# ledboard-r2.net
KiCad netlist of a schematic drawn in EAGLE
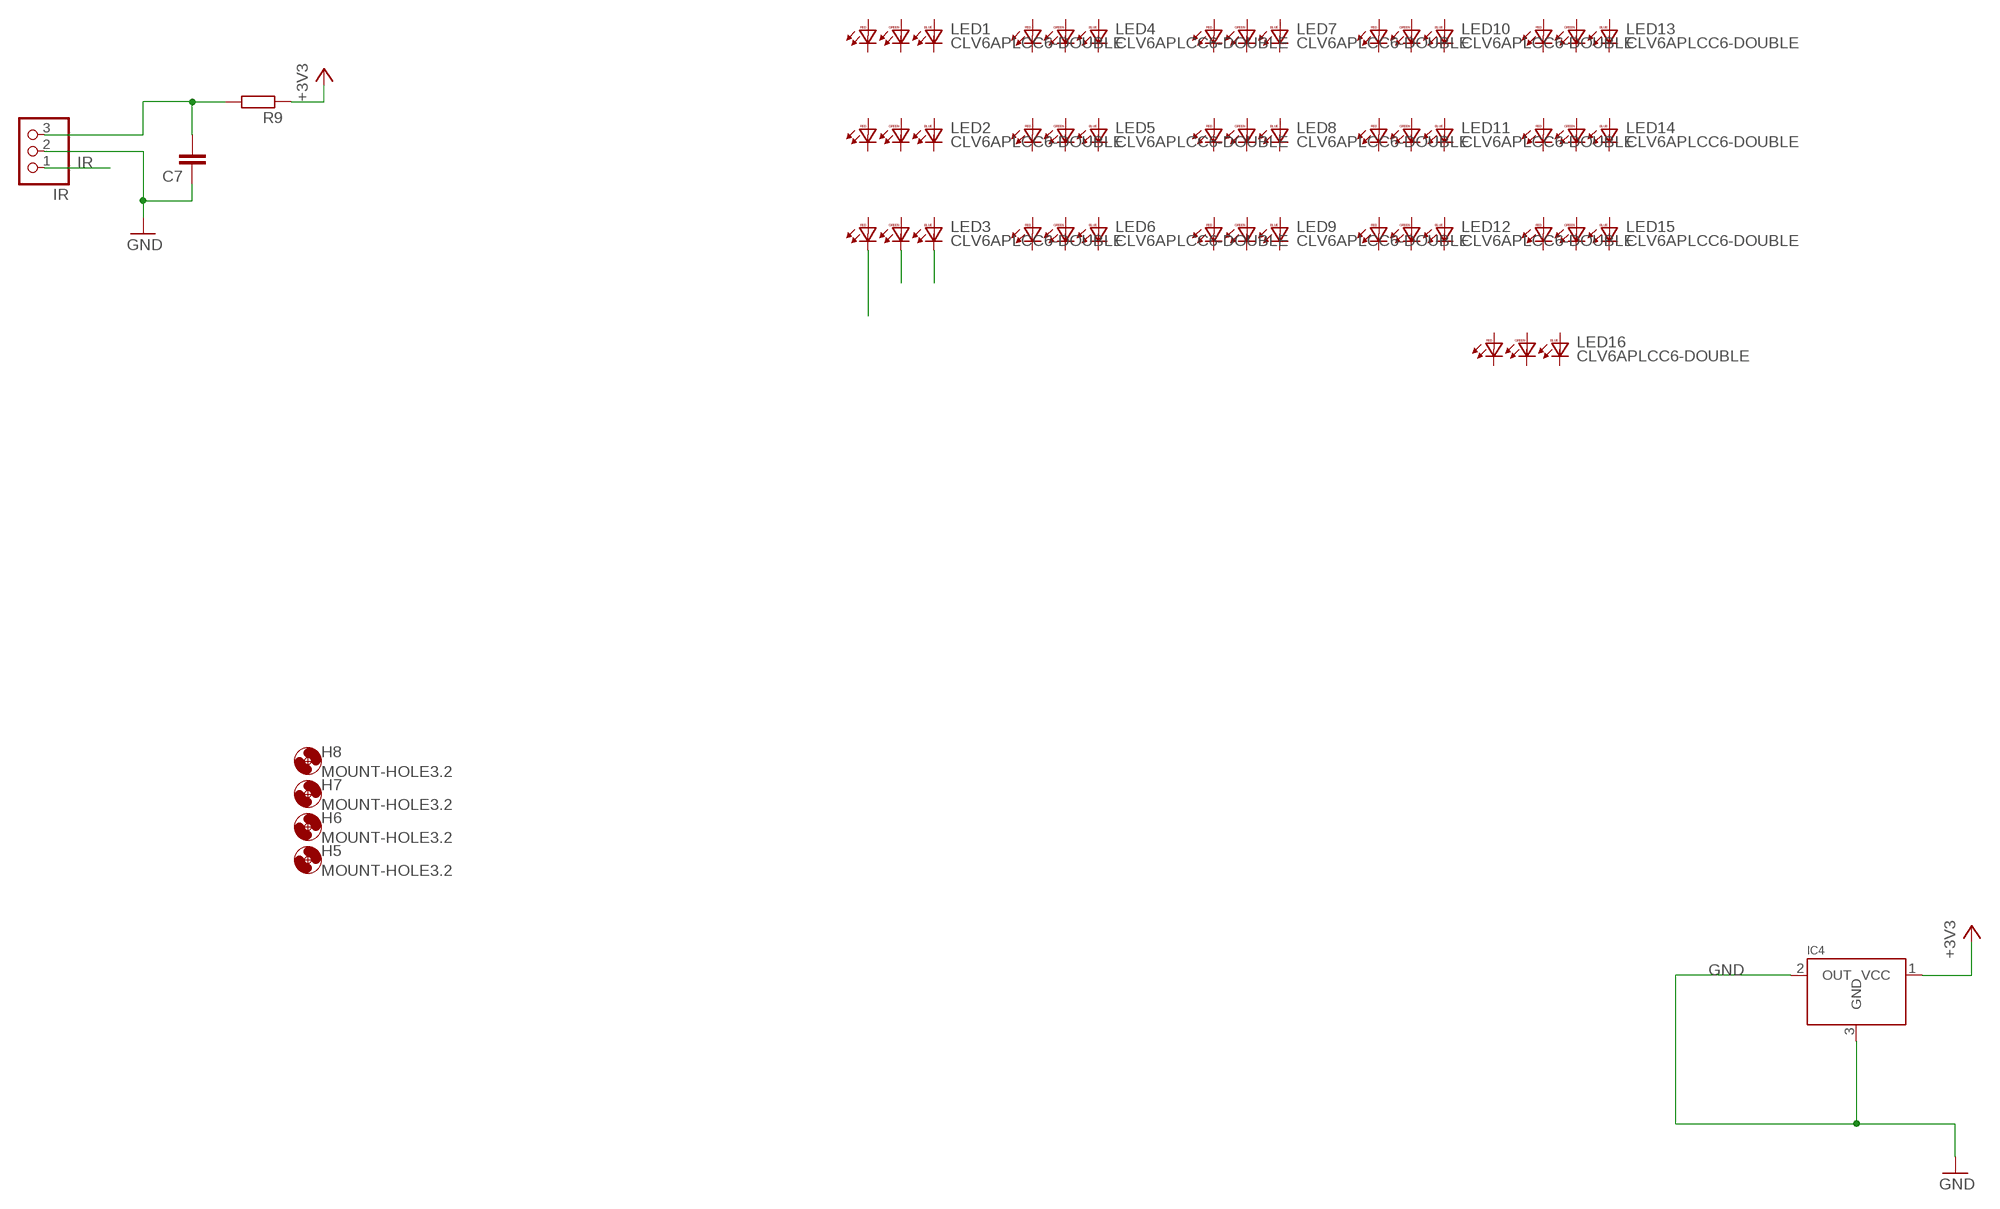
[diagram p0: schematic, sheet 1]

(export (version "E")
  (design (tool "Eeschema 10.0.6"))
  (components
    (comp (ref "C7")
      (value "C-EUC0805")
      (footprint "eagle-import:C0805")
      (libsource (lib "eagle-import") (part "C-EUC0805"))
    )
    (comp (ref "H5")
      (value "MOUNT-HOLE3.2")
      (footprint "eagle-import:3,2")
      (libsource (lib "eagle-import") (part "MOUNT-HOLE3.2"))
    )
    (comp (ref "H6")
      (value "MOUNT-HOLE3.2")
      (footprint "eagle-import:3,2")
      (libsource (lib "eagle-import") (part "MOUNT-HOLE3.2"))
    )
    (comp (ref "H7")
      (value "MOUNT-HOLE3.2")
      (footprint "eagle-import:3,2")
      (libsource (lib "eagle-import") (part "MOUNT-HOLE3.2"))
    )
    (comp (ref "H8")
      (value "MOUNT-HOLE3.2")
      (footprint "eagle-import:3,2")
      (libsource (lib "eagle-import") (part "MOUNT-HOLE3.2"))
    )
    (comp (ref "IC4")
      (value "MCP9701T-E/TTCTREFLOW")
      (footprint "eagle-import:SOT23-R")
      (libsource (lib "eagle-import") (part "MCP9701T-E/TTCTREFLOW"))
    )
    (comp (ref "IR")
      (value "PINHD-1X3")
      (footprint "eagle-import:1X03")
      (libsource (lib "eagle-import") (part "PINHD-1X3"))
    )
    (comp (ref "LED1")
      (value "CLV6APLCC6-DOUBLE")
      (footprint "eagle-import:PLCC6-DOUBLE")
      (libsource (lib "eagle-import") (part "CLV6APLCC6-DOUBLE"))
    )
    (comp (ref "LED2")
      (value "CLV6APLCC6-DOUBLE")
      (footprint "eagle-import:PLCC6-DOUBLE")
      (libsource (lib "eagle-import") (part "CLV6APLCC6-DOUBLE"))
    )
    (comp (ref "LED3")
      (value "CLV6APLCC6-DOUBLE")
      (footprint "eagle-import:PLCC6-DOUBLE")
      (libsource (lib "eagle-import") (part "CLV6APLCC6-DOUBLE"))
    )
    (comp (ref "LED4")
      (value "CLV6APLCC6-DOUBLE")
      (footprint "eagle-import:PLCC6-DOUBLE")
      (libsource (lib "eagle-import") (part "CLV6APLCC6-DOUBLE"))
    )
    (comp (ref "LED5")
      (value "CLV6APLCC6-DOUBLE")
      (footprint "eagle-import:PLCC6-DOUBLE")
      (libsource (lib "eagle-import") (part "CLV6APLCC6-DOUBLE"))
    )
    (comp (ref "LED6")
      (value "CLV6APLCC6-DOUBLE")
      (footprint "eagle-import:PLCC6-DOUBLE")
      (libsource (lib "eagle-import") (part "CLV6APLCC6-DOUBLE"))
    )
    (comp (ref "LED7")
      (value "CLV6APLCC6-DOUBLE")
      (footprint "eagle-import:PLCC6-DOUBLE")
      (libsource (lib "eagle-import") (part "CLV6APLCC6-DOUBLE"))
    )
    (comp (ref "LED8")
      (value "CLV6APLCC6-DOUBLE")
      (footprint "eagle-import:PLCC6-DOUBLE")
      (libsource (lib "eagle-import") (part "CLV6APLCC6-DOUBLE"))
    )
    (comp (ref "LED9")
      (value "CLV6APLCC6-DOUBLE")
      (footprint "eagle-import:PLCC6-DOUBLE")
      (libsource (lib "eagle-import") (part "CLV6APLCC6-DOUBLE"))
    )
    (comp (ref "LED10")
      (value "CLV6APLCC6-DOUBLE")
      (footprint "eagle-import:PLCC6-DOUBLE")
      (libsource (lib "eagle-import") (part "CLV6APLCC6-DOUBLE"))
    )
    (comp (ref "LED11")
      (value "CLV6APLCC6-DOUBLE")
      (footprint "eagle-import:PLCC6-DOUBLE")
      (libsource (lib "eagle-import") (part "CLV6APLCC6-DOUBLE"))
    )
    (comp (ref "LED12")
      (value "CLV6APLCC6-DOUBLE")
      (footprint "eagle-import:PLCC6-DOUBLE")
      (libsource (lib "eagle-import") (part "CLV6APLCC6-DOUBLE"))
    )
    (comp (ref "LED13")
      (value "CLV6APLCC6-DOUBLE")
      (footprint "eagle-import:PLCC6-DOUBLE")
      (libsource (lib "eagle-import") (part "CLV6APLCC6-DOUBLE"))
    )
    (comp (ref "LED14")
      (value "CLV6APLCC6-DOUBLE")
      (footprint "eagle-import:PLCC6-DOUBLE")
      (libsource (lib "eagle-import") (part "CLV6APLCC6-DOUBLE"))
    )
    (comp (ref "LED15")
      (value "CLV6APLCC6-DOUBLE")
      (footprint "eagle-import:PLCC6-DOUBLE")
      (libsource (lib "eagle-import") (part "CLV6APLCC6-DOUBLE"))
    )
    (comp (ref "LED16")
      (value "CLV6APLCC6-DOUBLE")
      (footprint "eagle-import:PLCC6-DOUBLE")
      (libsource (lib "eagle-import") (part "CLV6APLCC6-DOUBLE"))
    )
    (comp (ref "R9")
      (value "R-EU_R0805")
      (footprint "eagle-import:R0805")
      (libsource (lib "eagle-import") (part "R-EU_R0805"))
    )
  )
  (nets
    (net (code "1") (name "+3V3") (class "Default")
      (node (ref "IC4") (pin "1") (pinfunction "VCC_1") (pintype "power_in"))
      (node (ref "R9") (pin "1") (pinfunction "1_1") (pintype "passive"))
    )
    (net (code "2") (name "/IR") (class "Default")
      (node (ref "IR") (pin "1") (pinfunction "1_1") (pintype "passive"))
    )
    (net (code "3") (name "GND") (class "Default")
      (node (ref "C7") (pin "1") (pinfunction "1_1") (pintype "passive"))
      (node (ref "IC4") (pin "2") (pinfunction "OUT_2") (pintype "bidirectional"))
      (node (ref "IC4") (pin "3") (pinfunction "GND_3") (pintype "power_in"))
      (node (ref "IR") (pin "2") (pinfunction "2_2") (pintype "passive"))
    )
    (net (code "4") (name "Net-(C7-Pad2)") (class "Default")
      (node (ref "C7") (pin "2") (pinfunction "2_2") (pintype "passive"))
      (node (ref "IR") (pin "3") (pinfunction "3_3") (pintype "passive"))
      (node (ref "R9") (pin "2") (pinfunction "2_2") (pintype "passive"))
    )
    (net (code "5") (name "unconnected-(LED1-BA-Pad6)") (class "Default")
      (node (ref "LED1") (pin "6") (pinfunction "BA_6") (pintype "passive"))
    )
    (net (code "6") (name "unconnected-(LED1-BC-Pad1)") (class "Default")
      (node (ref "LED1") (pin "1") (pinfunction "BC_1") (pintype "passive"))
    )
    (net (code "7") (name "unconnected-(LED1-GA-Pad5)") (class "Default")
      (node (ref "LED1") (pin "5") (pinfunction "GA_5") (pintype "passive"))
    )
    (net (code "8") (name "unconnected-(LED1-GC-Pad2)") (class "Default")
      (node (ref "LED1") (pin "2") (pinfunction "GC_2") (pintype "passive"))
    )
    (net (code "9") (name "unconnected-(LED1-RA-Pad4)") (class "Default")
      (node (ref "LED1") (pin "4") (pinfunction "RA_4") (pintype "passive"))
    )
    (net (code "10") (name "unconnected-(LED1-RC-Pad3)") (class "Default")
      (node (ref "LED1") (pin "3") (pinfunction "RC_3") (pintype "passive"))
    )
    (net (code "11") (name "unconnected-(LED2-BA-Pad6)") (class "Default")
      (node (ref "LED2") (pin "6") (pinfunction "BA_6") (pintype "passive"))
    )
    (net (code "12") (name "unconnected-(LED2-BC-Pad1)") (class "Default")
      (node (ref "LED2") (pin "1") (pinfunction "BC_1") (pintype "passive"))
    )
    (net (code "13") (name "unconnected-(LED2-GA-Pad5)") (class "Default")
      (node (ref "LED2") (pin "5") (pinfunction "GA_5") (pintype "passive"))
    )
    (net (code "14") (name "unconnected-(LED2-GC-Pad2)") (class "Default")
      (node (ref "LED2") (pin "2") (pinfunction "GC_2") (pintype "passive"))
    )
    (net (code "15") (name "unconnected-(LED2-RA-Pad4)") (class "Default")
      (node (ref "LED2") (pin "4") (pinfunction "RA_4") (pintype "passive"))
    )
    (net (code "16") (name "unconnected-(LED2-RC-Pad3)") (class "Default")
      (node (ref "LED2") (pin "3") (pinfunction "RC_3") (pintype "passive"))
    )
    (net (code "17") (name "unconnected-(LED3-BA-Pad6)") (class "Default")
      (node (ref "LED3") (pin "6") (pinfunction "BA_6") (pintype "passive"))
    )
    (net (code "18") (name "unconnected-(LED3-BC-Pad1)") (class "Default")
      (node (ref "LED3") (pin "1") (pinfunction "BC_1") (pintype "passive"))
    )
    (net (code "19") (name "unconnected-(LED3-GA-Pad5)") (class "Default")
      (node (ref "LED3") (pin "5") (pinfunction "GA_5") (pintype "passive"))
    )
    (net (code "20") (name "unconnected-(LED3-GC-Pad2)") (class "Default")
      (node (ref "LED3") (pin "2") (pinfunction "GC_2") (pintype "passive"))
    )
    (net (code "21") (name "unconnected-(LED3-RA-Pad4)") (class "Default")
      (node (ref "LED3") (pin "4") (pinfunction "RA_4") (pintype "passive"))
    )
    (net (code "22") (name "unconnected-(LED3-RC-Pad3)") (class "Default")
      (node (ref "LED3") (pin "3") (pinfunction "RC_3") (pintype "passive"))
    )
    (net (code "23") (name "unconnected-(LED4-BA-Pad6)") (class "Default")
      (node (ref "LED4") (pin "6") (pinfunction "BA_6") (pintype "passive"))
    )
    (net (code "24") (name "unconnected-(LED4-BC-Pad1)") (class "Default")
      (node (ref "LED4") (pin "1") (pinfunction "BC_1") (pintype "passive"))
    )
    (net (code "25") (name "unconnected-(LED4-GA-Pad5)") (class "Default")
      (node (ref "LED4") (pin "5") (pinfunction "GA_5") (pintype "passive"))
    )
    (net (code "26") (name "unconnected-(LED4-GC-Pad2)") (class "Default")
      (node (ref "LED4") (pin "2") (pinfunction "GC_2") (pintype "passive"))
    )
    (net (code "27") (name "unconnected-(LED4-RA-Pad4)") (class "Default")
      (node (ref "LED4") (pin "4") (pinfunction "RA_4") (pintype "passive"))
    )
    (net (code "28") (name "unconnected-(LED4-RC-Pad3)") (class "Default")
      (node (ref "LED4") (pin "3") (pinfunction "RC_3") (pintype "passive"))
    )
    (net (code "29") (name "unconnected-(LED5-BA-Pad6)") (class "Default")
      (node (ref "LED5") (pin "6") (pinfunction "BA_6") (pintype "passive"))
    )
    (net (code "30") (name "unconnected-(LED5-BC-Pad1)") (class "Default")
      (node (ref "LED5") (pin "1") (pinfunction "BC_1") (pintype "passive"))
    )
    (net (code "31") (name "unconnected-(LED5-GA-Pad5)") (class "Default")
      (node (ref "LED5") (pin "5") (pinfunction "GA_5") (pintype "passive"))
    )
    (net (code "32") (name "unconnected-(LED5-GC-Pad2)") (class "Default")
      (node (ref "LED5") (pin "2") (pinfunction "GC_2") (pintype "passive"))
    )
    (net (code "33") (name "unconnected-(LED5-RA-Pad4)") (class "Default")
      (node (ref "LED5") (pin "4") (pinfunction "RA_4") (pintype "passive"))
    )
    (net (code "34") (name "unconnected-(LED5-RC-Pad3)") (class "Default")
      (node (ref "LED5") (pin "3") (pinfunction "RC_3") (pintype "passive"))
    )
    (net (code "35") (name "unconnected-(LED6-BA-Pad6)") (class "Default")
      (node (ref "LED6") (pin "6") (pinfunction "BA_6") (pintype "passive"))
    )
    (net (code "36") (name "unconnected-(LED6-BC-Pad1)") (class "Default")
      (node (ref "LED6") (pin "1") (pinfunction "BC_1") (pintype "passive"))
    )
    (net (code "37") (name "unconnected-(LED6-GA-Pad5)") (class "Default")
      (node (ref "LED6") (pin "5") (pinfunction "GA_5") (pintype "passive"))
    )
    (net (code "38") (name "unconnected-(LED6-GC-Pad2)") (class "Default")
      (node (ref "LED6") (pin "2") (pinfunction "GC_2") (pintype "passive"))
    )
    (net (code "39") (name "unconnected-(LED6-RA-Pad4)") (class "Default")
      (node (ref "LED6") (pin "4") (pinfunction "RA_4") (pintype "passive"))
    )
    (net (code "40") (name "unconnected-(LED6-RC-Pad3)") (class "Default")
      (node (ref "LED6") (pin "3") (pinfunction "RC_3") (pintype "passive"))
    )
    (net (code "41") (name "unconnected-(LED7-BA-Pad6)") (class "Default")
      (node (ref "LED7") (pin "6") (pinfunction "BA_6") (pintype "passive"))
    )
    (net (code "42") (name "unconnected-(LED7-BC-Pad1)") (class "Default")
      (node (ref "LED7") (pin "1") (pinfunction "BC_1") (pintype "passive"))
    )
    (net (code "43") (name "unconnected-(LED7-GA-Pad5)") (class "Default")
      (node (ref "LED7") (pin "5") (pinfunction "GA_5") (pintype "passive"))
    )
    (net (code "44") (name "unconnected-(LED7-GC-Pad2)") (class "Default")
      (node (ref "LED7") (pin "2") (pinfunction "GC_2") (pintype "passive"))
    )
    (net (code "45") (name "unconnected-(LED7-RA-Pad4)") (class "Default")
      (node (ref "LED7") (pin "4") (pinfunction "RA_4") (pintype "passive"))
    )
    (net (code "46") (name "unconnected-(LED7-RC-Pad3)") (class "Default")
      (node (ref "LED7") (pin "3") (pinfunction "RC_3") (pintype "passive"))
    )
    (net (code "47") (name "unconnected-(LED8-BA-Pad6)") (class "Default")
      (node (ref "LED8") (pin "6") (pinfunction "BA_6") (pintype "passive"))
    )
    (net (code "48") (name "unconnected-(LED8-BC-Pad1)") (class "Default")
      (node (ref "LED8") (pin "1") (pinfunction "BC_1") (pintype "passive"))
    )
    (net (code "49") (name "unconnected-(LED8-GA-Pad5)") (class "Default")
      (node (ref "LED8") (pin "5") (pinfunction "GA_5") (pintype "passive"))
    )
    (net (code "50") (name "unconnected-(LED8-GC-Pad2)") (class "Default")
      (node (ref "LED8") (pin "2") (pinfunction "GC_2") (pintype "passive"))
    )
    (net (code "51") (name "unconnected-(LED8-RA-Pad4)") (class "Default")
      (node (ref "LED8") (pin "4") (pinfunction "RA_4") (pintype "passive"))
    )
    (net (code "52") (name "unconnected-(LED8-RC-Pad3)") (class "Default")
      (node (ref "LED8") (pin "3") (pinfunction "RC_3") (pintype "passive"))
    )
    (net (code "53") (name "unconnected-(LED9-BA-Pad6)") (class "Default")
      (node (ref "LED9") (pin "6") (pinfunction "BA_6") (pintype "passive"))
    )
    (net (code "54") (name "unconnected-(LED9-BC-Pad1)") (class "Default")
      (node (ref "LED9") (pin "1") (pinfunction "BC_1") (pintype "passive"))
    )
    (net (code "55") (name "unconnected-(LED9-GA-Pad5)") (class "Default")
      (node (ref "LED9") (pin "5") (pinfunction "GA_5") (pintype "passive"))
    )
    (net (code "56") (name "unconnected-(LED9-GC-Pad2)") (class "Default")
      (node (ref "LED9") (pin "2") (pinfunction "GC_2") (pintype "passive"))
    )
    (net (code "57") (name "unconnected-(LED9-RA-Pad4)") (class "Default")
      (node (ref "LED9") (pin "4") (pinfunction "RA_4") (pintype "passive"))
    )
    (net (code "58") (name "unconnected-(LED9-RC-Pad3)") (class "Default")
      (node (ref "LED9") (pin "3") (pinfunction "RC_3") (pintype "passive"))
    )
    (net (code "59") (name "unconnected-(LED10-BA-Pad6)") (class "Default")
      (node (ref "LED10") (pin "6") (pinfunction "BA_6") (pintype "passive"))
    )
    (net (code "60") (name "unconnected-(LED10-BC-Pad1)") (class "Default")
      (node (ref "LED10") (pin "1") (pinfunction "BC_1") (pintype "passive"))
    )
    (net (code "61") (name "unconnected-(LED10-GA-Pad5)") (class "Default")
      (node (ref "LED10") (pin "5") (pinfunction "GA_5") (pintype "passive"))
    )
    (net (code "62") (name "unconnected-(LED10-GC-Pad2)") (class "Default")
      (node (ref "LED10") (pin "2") (pinfunction "GC_2") (pintype "passive"))
    )
    (net (code "63") (name "unconnected-(LED10-RA-Pad4)") (class "Default")
      (node (ref "LED10") (pin "4") (pinfunction "RA_4") (pintype "passive"))
    )
    (net (code "64") (name "unconnected-(LED10-RC-Pad3)") (class "Default")
      (node (ref "LED10") (pin "3") (pinfunction "RC_3") (pintype "passive"))
    )
    (net (code "65") (name "unconnected-(LED11-BA-Pad6)") (class "Default")
      (node (ref "LED11") (pin "6") (pinfunction "BA_6") (pintype "passive"))
    )
    (net (code "66") (name "unconnected-(LED11-BC-Pad1)") (class "Default")
      (node (ref "LED11") (pin "1") (pinfunction "BC_1") (pintype "passive"))
    )
    (net (code "67") (name "unconnected-(LED11-GA-Pad5)") (class "Default")
      (node (ref "LED11") (pin "5") (pinfunction "GA_5") (pintype "passive"))
    )
    (net (code "68") (name "unconnected-(LED11-GC-Pad2)") (class "Default")
      (node (ref "LED11") (pin "2") (pinfunction "GC_2") (pintype "passive"))
    )
    (net (code "69") (name "unconnected-(LED11-RA-Pad4)") (class "Default")
      (node (ref "LED11") (pin "4") (pinfunction "RA_4") (pintype "passive"))
    )
    (net (code "70") (name "unconnected-(LED11-RC-Pad3)") (class "Default")
      (node (ref "LED11") (pin "3") (pinfunction "RC_3") (pintype "passive"))
    )
    (net (code "71") (name "unconnected-(LED12-BA-Pad6)") (class "Default")
      (node (ref "LED12") (pin "6") (pinfunction "BA_6") (pintype "passive"))
    )
    (net (code "72") (name "unconnected-(LED12-BC-Pad1)") (class "Default")
      (node (ref "LED12") (pin "1") (pinfunction "BC_1") (pintype "passive"))
    )
    (net (code "73") (name "unconnected-(LED12-GA-Pad5)") (class "Default")
      (node (ref "LED12") (pin "5") (pinfunction "GA_5") (pintype "passive"))
    )
    (net (code "74") (name "unconnected-(LED12-GC-Pad2)") (class "Default")
      (node (ref "LED12") (pin "2") (pinfunction "GC_2") (pintype "passive"))
    )
    (net (code "75") (name "unconnected-(LED12-RA-Pad4)") (class "Default")
      (node (ref "LED12") (pin "4") (pinfunction "RA_4") (pintype "passive"))
    )
    (net (code "76") (name "unconnected-(LED12-RC-Pad3)") (class "Default")
      (node (ref "LED12") (pin "3") (pinfunction "RC_3") (pintype "passive"))
    )
    (net (code "77") (name "unconnected-(LED13-BA-Pad6)") (class "Default")
      (node (ref "LED13") (pin "6") (pinfunction "BA_6") (pintype "passive"))
    )
    (net (code "78") (name "unconnected-(LED13-BC-Pad1)") (class "Default")
      (node (ref "LED13") (pin "1") (pinfunction "BC_1") (pintype "passive"))
    )
    (net (code "79") (name "unconnected-(LED13-GA-Pad5)") (class "Default")
      (node (ref "LED13") (pin "5") (pinfunction "GA_5") (pintype "passive"))
    )
    (net (code "80") (name "unconnected-(LED13-GC-Pad2)") (class "Default")
      (node (ref "LED13") (pin "2") (pinfunction "GC_2") (pintype "passive"))
    )
    (net (code "81") (name "unconnected-(LED13-RA-Pad4)") (class "Default")
      (node (ref "LED13") (pin "4") (pinfunction "RA_4") (pintype "passive"))
    )
    (net (code "82") (name "unconnected-(LED13-RC-Pad3)") (class "Default")
      (node (ref "LED13") (pin "3") (pinfunction "RC_3") (pintype "passive"))
    )
    (net (code "83") (name "unconnected-(LED14-BA-Pad6)") (class "Default")
      (node (ref "LED14") (pin "6") (pinfunction "BA_6") (pintype "passive"))
    )
    (net (code "84") (name "unconnected-(LED14-BC-Pad1)") (class "Default")
      (node (ref "LED14") (pin "1") (pinfunction "BC_1") (pintype "passive"))
    )
    (net (code "85") (name "unconnected-(LED14-GA-Pad5)") (class "Default")
      (node (ref "LED14") (pin "5") (pinfunction "GA_5") (pintype "passive"))
    )
    (net (code "86") (name "unconnected-(LED14-GC-Pad2)") (class "Default")
      (node (ref "LED14") (pin "2") (pinfunction "GC_2") (pintype "passive"))
    )
    (net (code "87") (name "unconnected-(LED14-RA-Pad4)") (class "Default")
      (node (ref "LED14") (pin "4") (pinfunction "RA_4") (pintype "passive"))
    )
    (net (code "88") (name "unconnected-(LED14-RC-Pad3)") (class "Default")
      (node (ref "LED14") (pin "3") (pinfunction "RC_3") (pintype "passive"))
    )
    (net (code "89") (name "unconnected-(LED15-BA-Pad6)") (class "Default")
      (node (ref "LED15") (pin "6") (pinfunction "BA_6") (pintype "passive"))
    )
    (net (code "90") (name "unconnected-(LED15-BC-Pad1)") (class "Default")
      (node (ref "LED15") (pin "1") (pinfunction "BC_1") (pintype "passive"))
    )
    (net (code "91") (name "unconnected-(LED15-GA-Pad5)") (class "Default")
      (node (ref "LED15") (pin "5") (pinfunction "GA_5") (pintype "passive"))
    )
    (net (code "92") (name "unconnected-(LED15-GC-Pad2)") (class "Default")
      (node (ref "LED15") (pin "2") (pinfunction "GC_2") (pintype "passive"))
    )
    (net (code "93") (name "unconnected-(LED15-RA-Pad4)") (class "Default")
      (node (ref "LED15") (pin "4") (pinfunction "RA_4") (pintype "passive"))
    )
    (net (code "94") (name "unconnected-(LED15-RC-Pad3)") (class "Default")
      (node (ref "LED15") (pin "3") (pinfunction "RC_3") (pintype "passive"))
    )
    (net (code "95") (name "unconnected-(LED16-BA-Pad6)") (class "Default")
      (node (ref "LED16") (pin "6") (pinfunction "BA_6") (pintype "passive"))
    )
    (net (code "96") (name "unconnected-(LED16-BC-Pad1)") (class "Default")
      (node (ref "LED16") (pin "1") (pinfunction "BC_1") (pintype "passive"))
    )
    (net (code "97") (name "unconnected-(LED16-GA-Pad5)") (class "Default")
      (node (ref "LED16") (pin "5") (pinfunction "GA_5") (pintype "passive"))
    )
    (net (code "98") (name "unconnected-(LED16-GC-Pad2)") (class "Default")
      (node (ref "LED16") (pin "2") (pinfunction "GC_2") (pintype "passive"))
    )
    (net (code "99") (name "unconnected-(LED16-RA-Pad4)") (class "Default")
      (node (ref "LED16") (pin "4") (pinfunction "RA_4") (pintype "passive"))
    )
    (net (code "100") (name "unconnected-(LED16-RC-Pad3)") (class "Default")
      (node (ref "LED16") (pin "3") (pinfunction "RC_3") (pintype "passive"))
    )
  )
)
